# Motor_Drivers.net
KiCad netlist of a schematic drawn in EAGLE
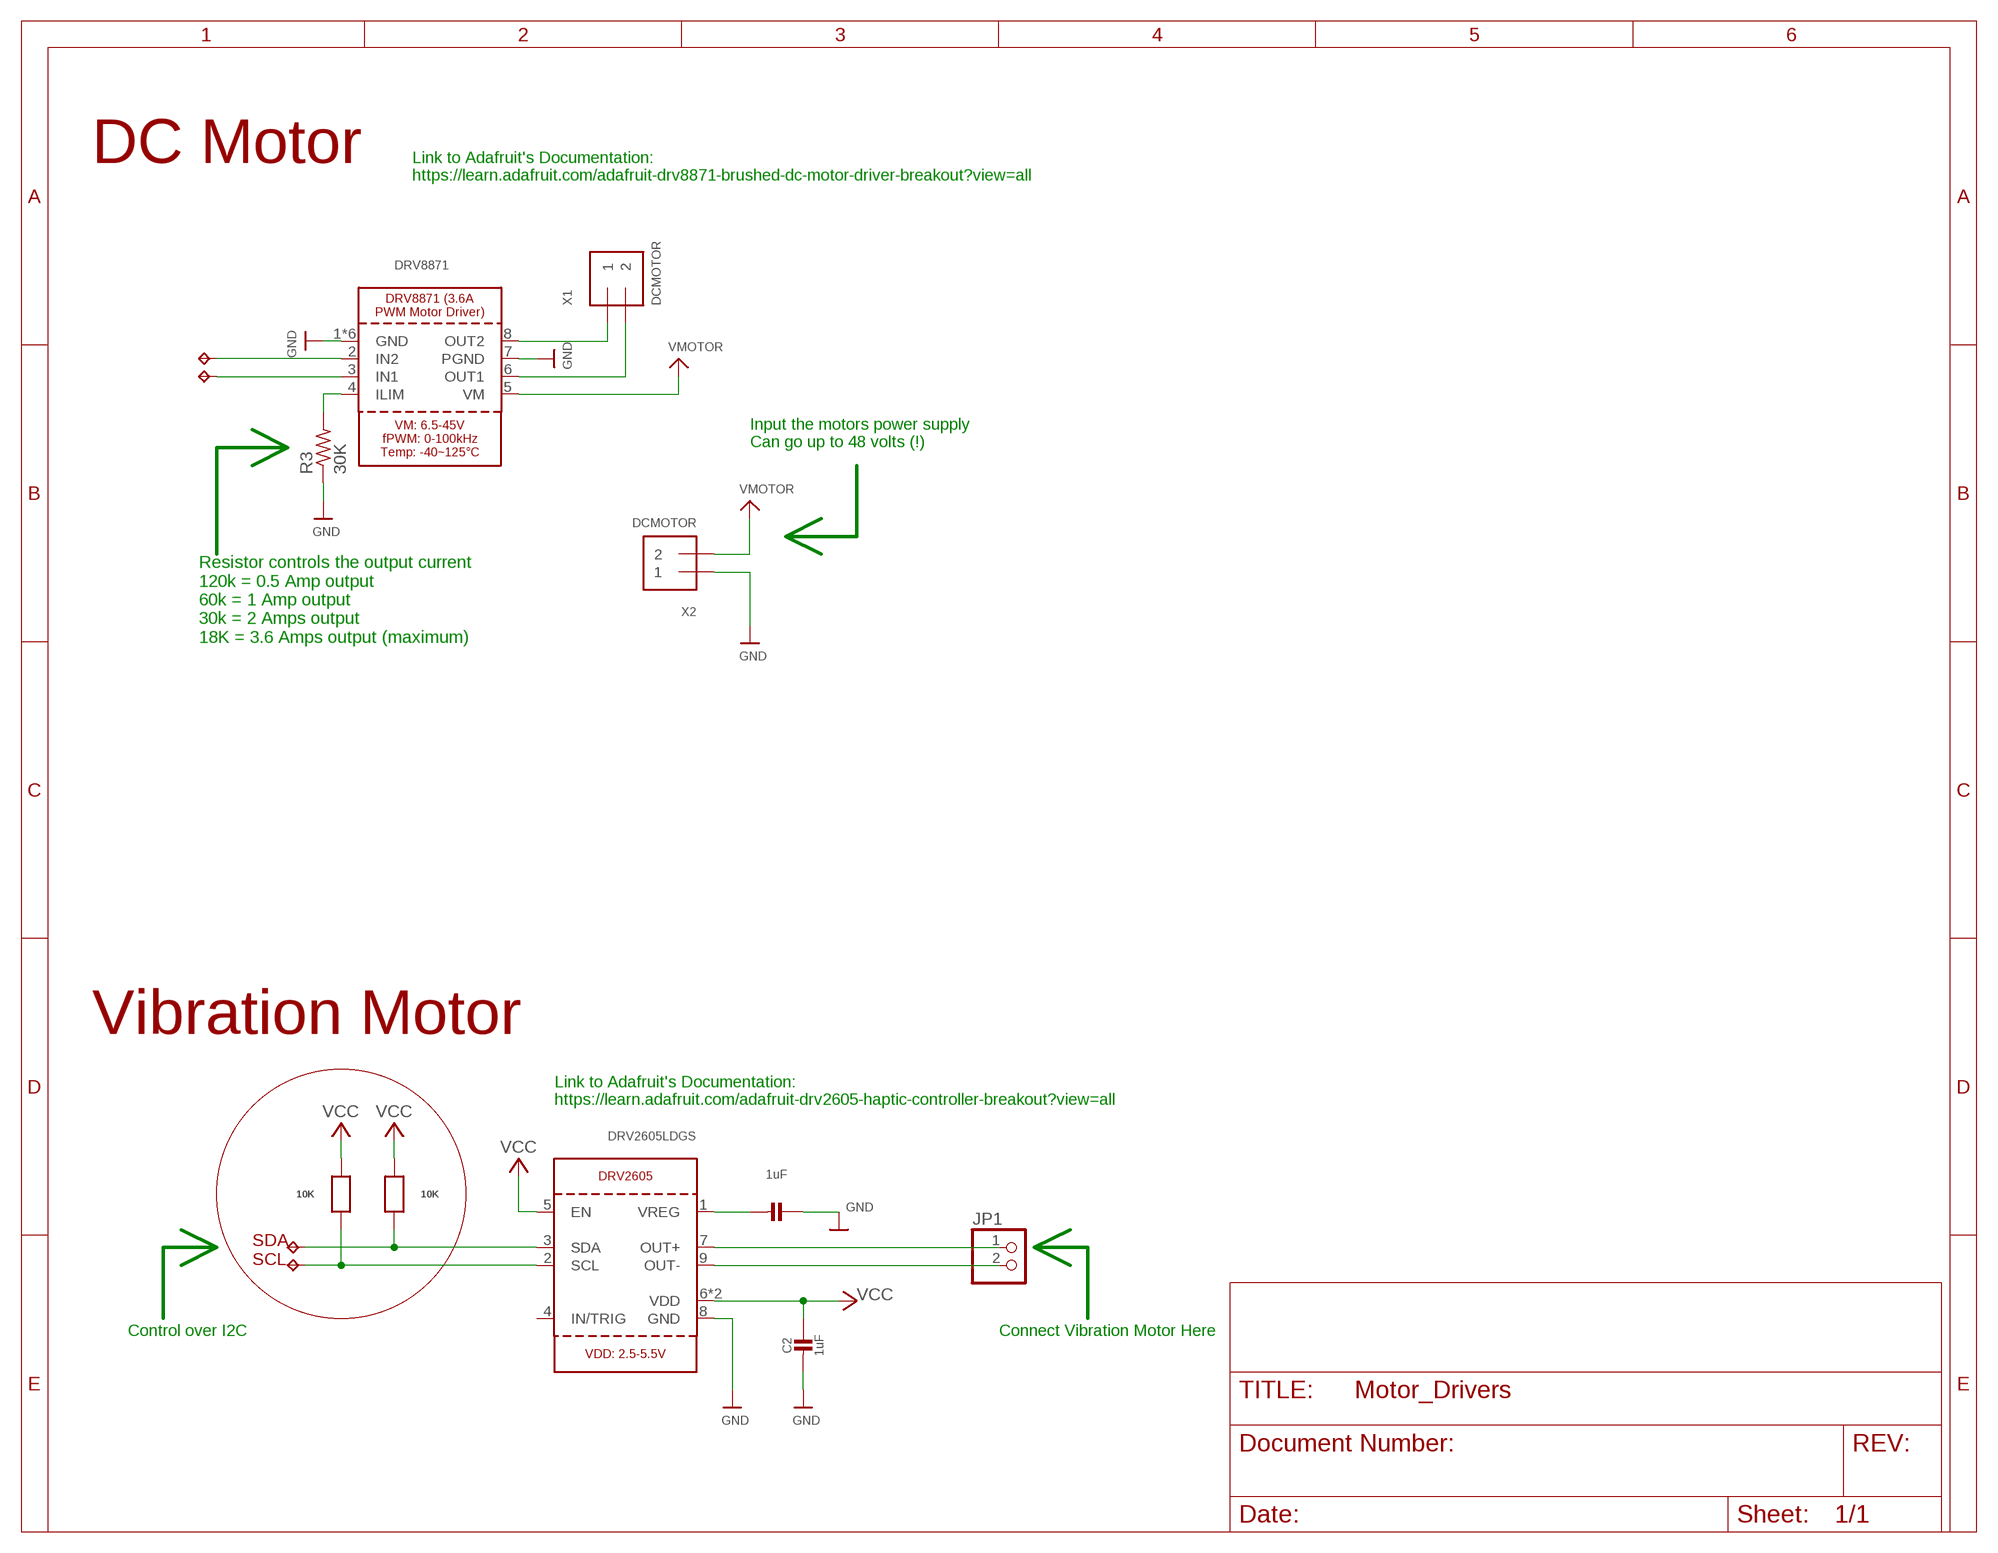
[diagram p0: schematic, sheet 1]

(export (version "E")
  (design (tool "Eeschema 10.0.6"))
  (components
    (comp (ref "C1")
      (value "1uF")
      (footprint "eagle-import:0805-NO")
      (libsource (lib "eagle-import") (part "CAP_CERAMIC0805-NOOUTLINE"))
    )
    (comp (ref "C2")
      (value "1uF")
      (footprint "eagle-import:0805-NO")
      (libsource (lib "eagle-import") (part "CAP_CERAMIC0805-NOOUTLINE"))
    )
    (comp (ref "JP1")
      (value "PINHD-1X2")
      (footprint "eagle-import:1X02")
      (libsource (lib "eagle-import") (part "PINHD-1X2"))
    )
    (comp (ref "R1")
      (value "10K")
      (footprint "eagle-import:0805-NO@1")
      (libsource (lib "eagle-import") (part "RESISTOR0805_NOOUTLINE"))
    )
    (comp (ref "R2")
      (value "10K")
      (footprint "eagle-import:0805-NO@1")
      (libsource (lib "eagle-import") (part "RESISTOR0805_NOOUTLINE"))
    )
    (comp (ref "R3")
      (value "30K")
      (footprint "eagle-import:0805-THM")
      (libsource (lib "eagle-import") (part "FLIPFLOP-RES"))
    )
    (comp (ref "TP1")
      (value "TPTP20R")
      (footprint "eagle-import:TP20R")
      (libsource (lib "eagle-import") (part "TPTP20R"))
    )
    (comp (ref "TP2")
      (value "TPTP20R")
      (footprint "eagle-import:TP20R")
      (libsource (lib "eagle-import") (part "TPTP20R"))
    )
    (comp (ref "TP3")
      (value "TPTP20R")
      (footprint "eagle-import:TP20R")
      (libsource (lib "eagle-import") (part "TPTP20R"))
    )
    (comp (ref "TP4")
      (value "TPTP20R")
      (footprint "eagle-import:TP20R")
      (libsource (lib "eagle-import") (part "TPTP20R"))
    )
    (comp (ref "U1")
      (value "DRV2605LDGS")
      (footprint "eagle-import:PSOP10")
      (libsource (lib "eagle-import") (part "DRV2605_SOP"))
    )
    (comp (ref "U2")
      (value "DRV8871")
      (footprint "eagle-import:HSOP8")
      (libsource (lib "eagle-import") (part "DRV8871"))
    )
    (comp (ref "X1")
      (value "DCMOTOR")
      (footprint "eagle-import:TERMBLOCK_1X2-3.5MM")
      (libsource (lib "eagle-import") (part "TERMBLOCK_1X2"))
    )
    (comp (ref "X2")
      (value "DCMOTOR")
      (footprint "eagle-import:TERMBLOCK_1X2-3.5MM")
      (libsource (lib "eagle-import") (part "TERMBLOCK_1X2"))
    )
  )
  (nets
    (net (code "1") (name "GND") (class "Default")
      (node (ref "C1") (pin "1") (pinfunction "1_1") (pintype "passive"))
      (node (ref "C2") (pin "2") (pinfunction "2_2") (pintype "passive"))
      (node (ref "R3") (pin "1") (pinfunction "1_1") (pintype "passive"))
      (node (ref "U1") (pin "8") (pinfunction "GND_8") (pintype "power_in"))
      (node (ref "U2") (pin "1") (pinfunction "GND_1") (pintype "power_in"))
      (node (ref "U2") (pin "7") (pinfunction "PGND_7") (pintype "power_in"))
      (node (ref "U2") (pin "GND") (pinfunction "GND_GND") (pintype "power_in"))
      (node (ref "U2") (pin "P$1") (pinfunction "GND_P$1") (pintype "power_in"))
      (node (ref "U2") (pin "P$2") (pinfunction "GND_P$2") (pintype "power_in"))
      (node (ref "U2") (pin "P$3") (pinfunction "GND_P$3") (pintype "power_in"))
      (node (ref "U2") (pin "P$4") (pinfunction "GND_P$4") (pintype "power_in"))
      (node (ref "X2") (pin "1") (pinfunction "1_1") (pintype "passive"))
    )
    (net (code "2") (name "Net-(U1-OUT+)") (class "Default")
      (node (ref "JP1") (pin "1") (pinfunction "1_1") (pintype "passive"))
      (node (ref "U1") (pin "7") (pinfunction "OUT+_7") (pintype "output"))
    )
    (net (code "3") (name "Net-(U1-OUT-)") (class "Default")
      (node (ref "JP1") (pin "2") (pinfunction "2_2") (pintype "passive"))
      (node (ref "U1") (pin "9") (pinfunction "OUT-_9") (pintype "output"))
    )
    (net (code "4") (name "Net-(U1-SCL)") (class "Default")
      (node (ref "R2") (pin "1") (pinfunction "1_1") (pintype "passive"))
      (node (ref "TP2") (pin "TP") (pinfunction "TP_TP") (pintype "input"))
      (node (ref "U1") (pin "2") (pinfunction "SCL_2") (pintype "input"))
    )
    (net (code "5") (name "Net-(U1-SDA)") (class "Default")
      (node (ref "R1") (pin "1") (pinfunction "1_1") (pintype "passive"))
      (node (ref "TP1") (pin "TP") (pinfunction "TP_TP") (pintype "input"))
      (node (ref "U1") (pin "3") (pinfunction "SDA_3") (pintype "bidirectional"))
    )
    (net (code "6") (name "Net-(U1-VREG)") (class "Default")
      (node (ref "C1") (pin "2") (pinfunction "2_2") (pintype "passive"))
      (node (ref "U1") (pin "1") (pinfunction "VREG_1") (pintype "output"))
    )
    (net (code "7") (name "Net-(U2-ILIM)") (class "Default")
      (node (ref "R3") (pin "2") (pinfunction "2_2") (pintype "passive"))
      (node (ref "U2") (pin "4") (pinfunction "ILIM_4") (pintype "input"))
    )
    (net (code "8") (name "Net-(U2-IN1)") (class "Default")
      (node (ref "TP4") (pin "TP") (pinfunction "TP_TP") (pintype "input"))
      (node (ref "U2") (pin "3") (pinfunction "IN1_3") (pintype "input"))
    )
    (net (code "9") (name "Net-(U2-IN2)") (class "Default")
      (node (ref "TP3") (pin "TP") (pinfunction "TP_TP") (pintype "input"))
      (node (ref "U2") (pin "2") (pinfunction "IN2_2") (pintype "input"))
    )
    (net (code "10") (name "Net-(U2-OUT1)") (class "Default")
      (node (ref "U2") (pin "6") (pinfunction "OUT1_6") (pintype "output"))
      (node (ref "X1") (pin "2") (pinfunction "2_2") (pintype "passive"))
    )
    (net (code "11") (name "Net-(U2-OUT2)") (class "Default")
      (node (ref "U2") (pin "8") (pinfunction "OUT2_8") (pintype "output"))
      (node (ref "X1") (pin "1") (pinfunction "1_1") (pintype "passive"))
    )
    (net (code "12") (name "VCC") (class "Default")
      (node (ref "C2") (pin "1") (pinfunction "1_1") (pintype "passive"))
      (node (ref "R1") (pin "2") (pinfunction "2_2") (pintype "passive"))
      (node (ref "R2") (pin "2") (pinfunction "2_2") (pintype "passive"))
      (node (ref "U1") (pin "10") (pinfunction "VDD_10") (pintype "power_in"))
      (node (ref "U1") (pin "5") (pinfunction "EN_5") (pintype "input"))
      (node (ref "U1") (pin "6") (pinfunction "VDD_6") (pintype "power_in"))
    )
    (net (code "13") (name "VMOTOR") (class "Default")
      (node (ref "U2") (pin "5") (pinfunction "VM_5") (pintype "power_in"))
      (node (ref "X2") (pin "2") (pinfunction "2_2") (pintype "passive"))
    )
    (net (code "14") (name "unconnected-(U1-IN{slash}TRIG-Pad4)") (class "Default")
      (node (ref "U1") (pin "4") (pinfunction "IN/TRIG_4") (pintype "input"))
    )
  )
)
